# GD_Power_Meter_2.net
KiCad netlist of a schematic drawn in Altium Designer
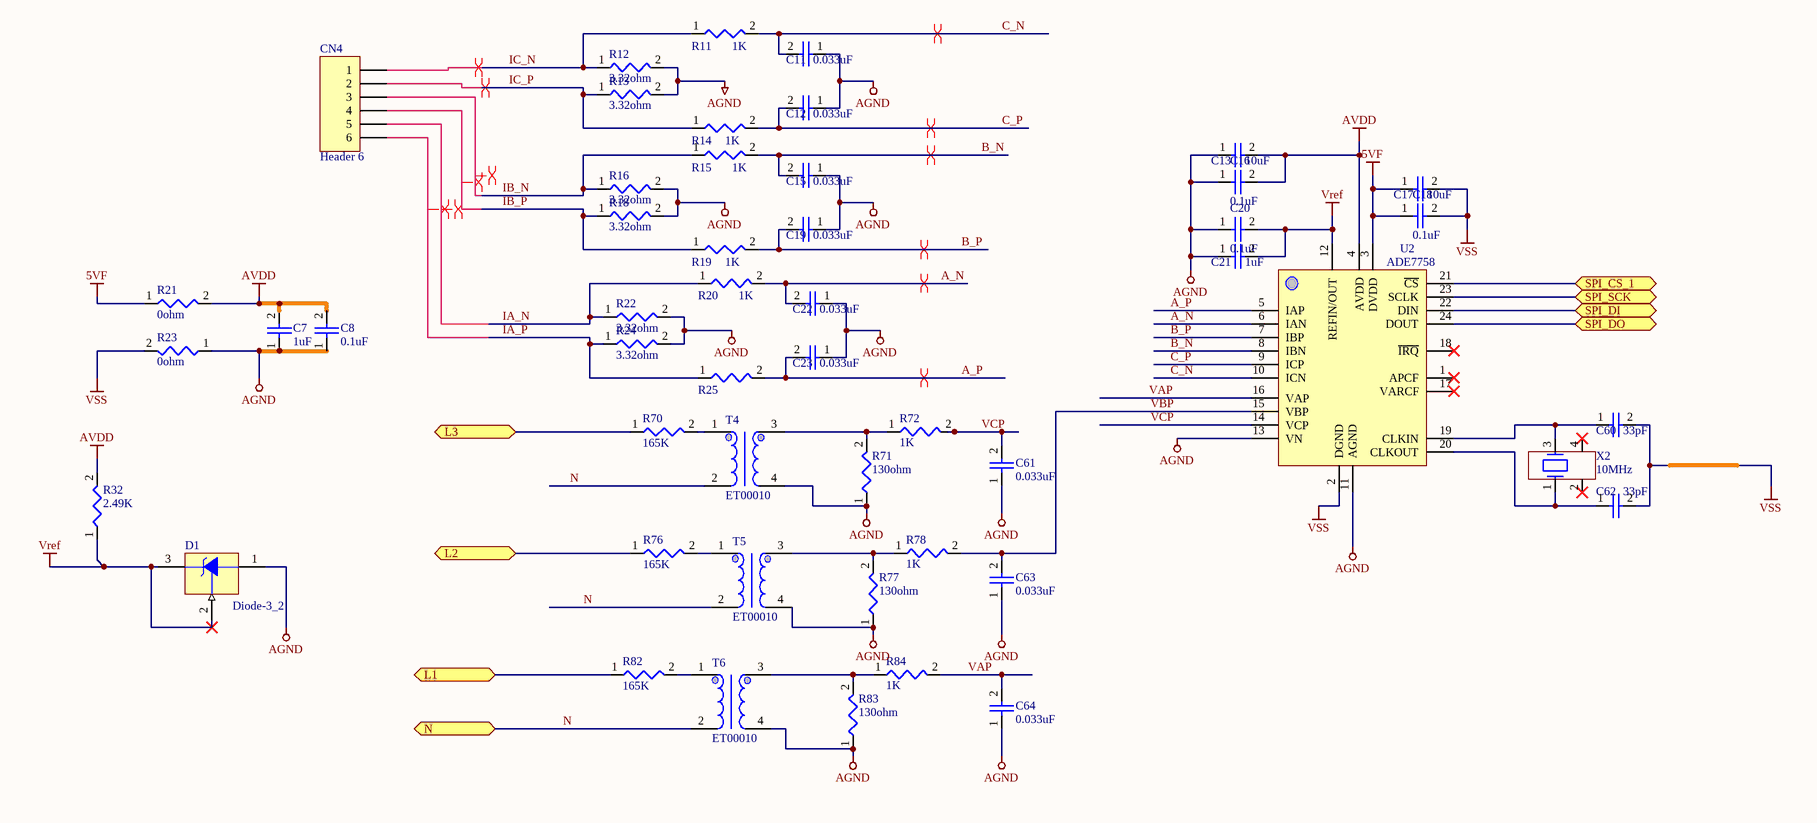
[diagram p0: GD_Power_Meter_2.SchDoc]

(export (version "E")
  (design (tool "Eeschema 10.0.6"))
  (components
    (comp (ref "C7")
      (value "1uF")
      (footprint "C0805")
      (description "CAP SMD CR X7R 50V 10% 1uF 0805 ROHS")
      (fields (field (name "MANUFACTURER") "YAGEO") (field (name "Comment") "CAP"))
      (libsource (lib "enlogic") (part "CAP"))
    )
    (comp (ref "C8")
      (value "0.1uF")
      (footprint "C0805")
      (description "CAP SMD CR X7R 50V 10% 0.1uF 0805 ROHS")
      (fields (field (name "MANUFACTURER") "YAGEO") (field (name "Comment") "CAP"))
      (libsource (lib "enlogic") (part "CAP"))
    )
    (comp (ref "C11")
      (value "0.033uF")
      (footprint "C0805")
      (description "CAP SMD X7R 50V 10% 0.033uF 0805 ROHS")
      (fields (field (name "MANUFACTURER") "Murata") (field (name "Comment") "CAP"))
      (libsource (lib "enlogic") (part "CAP"))
    )
    (comp (ref "C12")
      (value "0.033uF")
      (footprint "C0805")
      (description "CAP SMD X7R 50V 10% 0.033uF 0805 ROHS")
      (fields (field (name "MANUFACTURER") "Murata") (field (name "Comment") "CAP"))
      (libsource (lib "enlogic") (part "CAP"))
    )
    (comp (ref "C13")
      (value "10uF")
      (footprint "C0805")
      (description "CAP SMD CR X5R 16V 10% 10uF 0805 ROHS")
      (fields (field (name "MANUFACTURER") "Murata"))
      (libsource (lib "enlogic") (part "CAP"))
    )
    (comp (ref "C15")
      (value "0.033uF")
      (footprint "C0805")
      (description "CAP SMD X7R 50V 10% 0.033uF 0805 ROHS")
      (fields (field (name "MANUFACTURER") "Murata") (field (name "Comment") "CAP"))
      (libsource (lib "enlogic") (part "CAP"))
    )
    (comp (ref "C16")
      (value "0.1uF")
      (footprint "C0805")
      (description "CAP SMD CR X7R 50V 10% 0.1uF 0805 ROHS")
      (fields (field (name "MANUFACTURER") "YAGEO") (field (name "Comment") "CAP"))
      (libsource (lib "enlogic") (part "CAP"))
    )
    (comp (ref "C17")
      (value "10uF")
      (footprint "C0805")
      (description "CAP SMD CR X5R 16V 10% 10uF 0805 ROHS")
      (fields (field (name "MANUFACTURER") "Murata"))
      (libsource (lib "enlogic") (part "CAP"))
    )
    (comp (ref "C18")
      (value "0.1uF")
      (footprint "C0805")
      (description "CAP SMD CR X7R 50V 10% 0.1uF 0805 ROHS")
      (fields (field (name "MANUFACTURER") "YAGEO") (field (name "Comment") "CAP"))
      (libsource (lib "enlogic") (part "CAP"))
    )
    (comp (ref "C19")
      (value "0.033uF")
      (footprint "C0805")
      (description "CAP SMD X7R 50V 10% 0.033uF 0805 ROHS")
      (fields (field (name "MANUFACTURER") "Murata") (field (name "Comment") "CAP"))
      (libsource (lib "enlogic") (part "CAP"))
    )
    (comp (ref "C20")
      (value "0.1uF")
      (footprint "C0805")
      (description "CAP SMD CR X7R 50V 10% 0.1uF 0805 ROHS")
      (fields (field (name "MANUFACTURER") "YAGEO") (field (name "Comment") "CAP"))
      (libsource (lib "enlogic") (part "CAP"))
    )
    (comp (ref "C21")
      (value "1uF")
      (footprint "C0805")
      (description "CAP SMD CR X7R 50V 10% 1uF 0805 ROHS")
      (fields (field (name "MANUFACTURER") "YAGEO") (field (name "Comment") "CAP"))
      (libsource (lib "enlogic") (part "CAP"))
    )
    (comp (ref "C22")
      (value "0.033uF")
      (footprint "C0805")
      (description "CAP SMD X7R 50V 10% 0.033uF 0805 ROHS")
      (fields (field (name "MANUFACTURER") "Murata") (field (name "Comment") "CAP"))
      (libsource (lib "enlogic") (part "CAP"))
    )
    (comp (ref "C23")
      (value "0.033uF")
      (footprint "C0805")
      (description "CAP SMD X7R 50V 10% 0.033uF 0805 ROHS")
      (fields (field (name "MANUFACTURER") "Murata") (field (name "Comment") "CAP"))
      (libsource (lib "enlogic") (part "CAP"))
    )
    (comp (ref "C60")
      (value "33pF")
      (footprint "C0805")
      (description "CAP SMD C0G 50V 5% 33pF 0805 ROHS")
      (fields (field (name "MANUFACTURER") "YAGEO") (field (name "Comment") "CAP"))
      (libsource (lib "enlogic") (part "CAP"))
    )
    (comp (ref "C61")
      (value "0.033uF")
      (footprint "C0805")
      (description "CAP SMD X7R 50V 10% 0.033uF 0805 ROHS")
      (fields (field (name "MANUFACTURER") "Murata") (field (name "Comment") "CAP"))
      (libsource (lib "enlogic") (part "CAP"))
    )
    (comp (ref "C62")
      (value "33pF")
      (footprint "C0805")
      (description "CAP SMD C0G 50V 5% 33pF 0805 ROHS")
      (fields (field (name "MANUFACTURER") "YAGEO") (field (name "Comment") "CAP"))
      (libsource (lib "enlogic") (part "CAP"))
    )
    (comp (ref "C63")
      (value "0.033uF")
      (footprint "C0805")
      (description "CAP SMD X7R 50V 10% 0.033uF 0805 ROHS")
      (fields (field (name "MANUFACTURER") "Murata") (field (name "Comment") "CAP"))
      (libsource (lib "enlogic") (part "CAP"))
    )
    (comp (ref "C64")
      (value "0.033uF")
      (footprint "C0805")
      (description "CAP SMD X7R 50V 10% 0.033uF 0805 ROHS")
      (fields (field (name "MANUFACTURER") "Murata") (field (name "Comment") "CAP"))
      (libsource (lib "enlogic") (part "CAP"))
    )
    (comp (ref "CN4")
      (value "Header 6")
      (footprint "HT5.08-6P-H")
      (description "Header, 6-Pin")
      (libsource (lib "Enlogic_CN") (part "Header 6"))
    )
    (comp (ref "D1")
      (value "Diode-3_2")
      (footprint "SOT23-321")
      (description "IC PROGRAMMABLE PRECISION REFERENCES,2.5-20V,0.5%,SMD,ROHS")
      (fields (field (name "MANUFACTURER") "DIODES"))
      (libsource (lib "enlogic") (part "ZTL43X"))
    )
    (comp (ref "R11")
      (value "1K")
      (footprint "R0805")
      (description "RES THICK_FILM SMD 1K 1% 1/8W ROHS 0805")
      (fields (field (name "MANUFACTURER") "YAGEO") (field (name "Comment") "RES"))
      (libsource (lib "enlogic") (part "RES"))
    )
    (comp (ref "R12")
      (value "3.32ohm")
      (footprint "R0805")
      (description "RES THIN_FILM SMD 3.32 ohm 0.5% 1/8W ±50ppm/℃ ROHS 0805")
      (fields (field (name "MANUFACTURER") "YAGEO") (field (name "Comment") "RES"))
      (libsource (lib "Enlogic") (part "RES"))
    )
    (comp (ref "R13")
      (value "3.32ohm")
      (footprint "R0805")
      (description "RES THIN_FILM SMD 3.32 ohm 0.5% 1/8W ±50ppm/℃ ROHS 0805")
      (fields (field (name "MANUFACTURER") "YAGEO") (field (name "Comment") "RES"))
      (libsource (lib "Enlogic") (part "RES"))
    )
    (comp (ref "R14")
      (value "1K")
      (footprint "R0805")
      (description "RES THICK_FILM SMD 1K 1% 1/8W ROHS 0805")
      (fields (field (name "MANUFACTURER") "YAGEO") (field (name "Comment") "RES"))
      (libsource (lib "enlogic") (part "RES"))
    )
    (comp (ref "R15")
      (value "1K")
      (footprint "R0805")
      (description "RES THICK_FILM SMD 1K 1% 1/8W ROHS 0805")
      (fields (field (name "MANUFACTURER") "YAGEO") (field (name "Comment") "RES"))
      (libsource (lib "enlogic") (part "RES"))
    )
    (comp (ref "R16")
      (value "3.32ohm")
      (footprint "R0805")
      (description "RES THIN_FILM SMD 3.32 ohm 0.5% 1/8W ±50ppm/℃ ROHS 0805")
      (fields (field (name "MANUFACTURER") "YAGEO") (field (name "Comment") "RES"))
      (libsource (lib "Enlogic") (part "RES"))
    )
    (comp (ref "R18")
      (value "3.32ohm")
      (footprint "R0805")
      (description "RES THIN_FILM SMD 3.32 ohm 0.5% 1/8W ±50ppm/℃ ROHS 0805")
      (fields (field (name "MANUFACTURER") "YAGEO") (field (name "Comment") "RES"))
      (libsource (lib "Enlogic") (part "RES"))
    )
    (comp (ref "R19")
      (value "1K")
      (footprint "R0805")
      (description "RES THICK_FILM SMD 1K 1% 1/8W ROHS 0805")
      (fields (field (name "MANUFACTURER") "YAGEO") (field (name "Comment") "RES"))
      (libsource (lib "enlogic") (part "RES"))
    )
    (comp (ref "R20")
      (value "1K")
      (footprint "R0805")
      (description "RES THICK_FILM SMD 1K 1% 1/8W ROHS 0805")
      (fields (field (name "MANUFACTURER") "YAGEO") (field (name "Comment") "RES"))
      (libsource (lib "enlogic") (part "RES"))
    )
    (comp (ref "R21")
      (value "0ohm")
      (footprint "R0805")
      (description "RES THICK_FILM SMD 0 OHM 5% 1/8W ROHS 0805")
      (fields (field (name "MANUFACTURER") "YAGEO") (field (name "Comment") "RES"))
      (libsource (lib "enlogic") (part "RES"))
    )
    (comp (ref "R22")
      (value "3.32ohm")
      (footprint "R0805")
      (description "RES THIN_FILM SMD 3.32 ohm 0.5% 1/8W ±50ppm/℃ ROHS 0805")
      (fields (field (name "MANUFACTURER") "YAGEO") (field (name "Comment") "RES"))
      (libsource (lib "Enlogic") (part "RES"))
    )
    (comp (ref "R23")
      (value "0ohm")
      (footprint "R0805")
      (description "RES THICK_FILM SMD 0 OHM 5% 1/8W ROHS 0805")
      (fields (field (name "MANUFACTURER") "YAGEO") (field (name "Comment") "RES"))
      (libsource (lib "enlogic") (part "RES"))
    )
    (comp (ref "R24")
      (value "3.32ohm")
      (footprint "R0805")
      (description "RES THIN_FILM SMD 3.32 ohm 0.5% 1/8W ±50ppm/℃ ROHS 0805")
      (fields (field (name "MANUFACTURER") "YAGEO") (field (name "Comment") "RES"))
      (libsource (lib "Enlogic") (part "RES"))
    )
    (comp (ref "R25")
      (value "RES")
      (footprint "R0805")
      (description "RES THICK_FILM SMD 1K 1% 1/8W ROHS 0805")
      (fields (field (name "MANUFACTURER") "YAGEO"))
      (libsource (lib "enlogic") (part "RES"))
    )
    (comp (ref "R32")
      (value "2.49K")
      (footprint "R0805")
      (description "RES THICK_FILM 2.49K 1% 1/8W ROHS SMD 0805")
      (fields (field (name "MANUFACTURER") "YAGEO") (field (name "Comment") "RES"))
      (libsource (lib "enlogic") (part "RES"))
    )
    (comp (ref "R70")
      (value "165K")
      (footprint "MFR5W2P5")
      (description "RES Film Leaded 165K 0.5% 3W ROHS ±25ppm/℃ MFR1550")
      (fields (field (name "MANUFACTURER") "Viking") (field (name "Comment") "RES"))
      (libsource (lib "Enlogic") (part "RES"))
    )
    (comp (ref "R71")
      (value "130ohm")
      (footprint "R0805")
      (description "RES,THIN_FILM,130 ohm,0.5%	,1/10W,±25ppm/℃,ROHS,0805,SMD")
      (fields (field (name "MANUFACTURER") "VIKING") (field (name "Comment") "RES"))
      (libsource (lib "Enlogic") (part "RES"))
    )
    (comp (ref "R72")
      (value "1K")
      (footprint "R0805")
      (description "RES THICK_FILM SMD 1K 1% 1/8W ROHS 0805")
      (fields (field (name "MANUFACTURER") "YAGEO") (field (name "Comment") "RES"))
      (libsource (lib "Enlogic") (part "RES"))
    )
    (comp (ref "R76")
      (value "165K")
      (footprint "MFR5W2P5")
      (description "RES Film Leaded 165K 0.5% 3W ROHS ±25ppm/℃ MFR1550")
      (fields (field (name "MANUFACTURER") "Viking") (field (name "Comment") "RES"))
      (libsource (lib "Enlogic") (part "RES"))
    )
    (comp (ref "R77")
      (value "130ohm")
      (footprint "R0805")
      (description "RES,THIN_FILM,130 ohm,0.5%	,1/10W,±25ppm/℃,ROHS,0805,SMD")
      (fields (field (name "MANUFACTURER") "VIKING") (field (name "Comment") "RES"))
      (libsource (lib "Enlogic") (part "RES"))
    )
    (comp (ref "R78")
      (value "1K")
      (footprint "R0805")
      (description "RES THICK_FILM SMD 1K 1% 1/8W ROHS 0805")
      (fields (field (name "MANUFACTURER") "YAGEO") (field (name "Comment") "RES"))
      (libsource (lib "Enlogic") (part "RES"))
    )
    (comp (ref "R82")
      (value "165K")
      (footprint "MFR5W2P5")
      (description "RES Film Leaded 165K 0.5% 3W ROHS ±25ppm/℃ MFR1550")
      (fields (field (name "MANUFACTURER") "Viking") (field (name "Comment") "RES"))
      (libsource (lib "Enlogic") (part "RES"))
    )
    (comp (ref "R83")
      (value "130ohm")
      (footprint "R0805")
      (description "RES,THIN_FILM,130 ohm,0.5%	,1/10W,±25ppm/℃,ROHS,0805,SMD")
      (fields (field (name "MANUFACTURER") "VIKING") (field (name "Comment") "RES"))
      (libsource (lib "Enlogic") (part "RES"))
    )
    (comp (ref "R84")
      (value "1K")
      (footprint "R0805")
      (description "RES THICK_FILM SMD 1K 1% 1/8W ROHS 0805")
      (fields (field (name "MANUFACTURER") "YAGEO") (field (name "Comment") "RES"))
      (libsource (lib "Enlogic") (part "RES"))
    )
    (comp (ref "T4")
      (value "ET00010")
      (footprint "ZMPT107")
      (description "Voltage transformer,2mA/2mA,THT,ROHS")
      (fields (field (name "MANUFACTURER") "ZEMING"))
      (libsource (lib "Enlogic") (part "ZMPT107"))
    )
    (comp (ref "T5")
      (value "ET00010")
      (footprint "ZMPT107")
      (description "Voltage transformer,2mA/2mA,THT,ROHS")
      (fields (field (name "MANUFACTURER") "ZEMING"))
      (libsource (lib "Enlogic") (part "ZMPT107"))
    )
    (comp (ref "T6")
      (value "ET00010")
      (footprint "ZMPT107")
      (description "Voltage transformer,2mA/2mA,THT,ROHS")
      (fields (field (name "MANUFACTURER") "ZEMING"))
      (libsource (lib "Enlogic") (part "ZMPT107"))
    )
    (comp (ref "U2")
      (value "ADE7758")
      (footprint "SOIC24-W")
      (description "IC Energy Measurement,Irms,VA,VAR,Vrms,Watt,Output:Pulsed&SPI,SOIC_W-24,ROHS")
      (fields (field (name "MANUFACTURER") "ANALOG DEVICES"))
      (libsource (lib "enlogic") (part "ADE7758"))
    )
    (comp (ref "X2")
      (value "10MHz")
      (footprint "XTAL_5X3_2")
      (description "XTAL 10MHz 18PF +/-30PPM,3.2mmWx5mmLx1.3mmH,-40~85,RoHS,SMD")
      (fields (field (name "MANUFACTURER") "ABRACON") (field (name "Comment") "ABM3C"))
      (libsource (lib "enlogic") (part "ABM3C"))
    )
  )
  (nets
    (net (code "1") (name "/A_N") (class "Default")
      (node (ref "C22") (pin "2") (pinfunction "2_2") (pintype "passive"))
      (node (ref "R20") (pin "2") (pinfunction "2_2") (pintype "passive"))
      (node (ref "U2") (pin "6") (pinfunction "IAN_6") (pintype "passive"))
    )
    (net (code "2") (name "/A_P") (class "Default")
      (node (ref "C23") (pin "2") (pinfunction "2_2") (pintype "passive"))
      (node (ref "R25") (pin "2") (pinfunction "2_2") (pintype "passive"))
      (node (ref "U2") (pin "5") (pinfunction "IAP_5") (pintype "passive"))
    )
    (net (code "3") (name "/B_N") (class "Default")
      (node (ref "C15") (pin "2") (pinfunction "2_2") (pintype "passive"))
      (node (ref "R15") (pin "2") (pinfunction "2_2") (pintype "passive"))
      (node (ref "U2") (pin "8") (pinfunction "IBN_8") (pintype "passive"))
    )
    (net (code "4") (name "/B_P") (class "Default")
      (node (ref "C19") (pin "2") (pinfunction "2_2") (pintype "passive"))
      (node (ref "R19") (pin "2") (pinfunction "2_2") (pintype "passive"))
      (node (ref "U2") (pin "7") (pinfunction "IBP_7") (pintype "passive"))
    )
    (net (code "5") (name "/C_N") (class "Default")
      (node (ref "C11") (pin "2") (pinfunction "2_2") (pintype "passive"))
      (node (ref "R11") (pin "2") (pinfunction "2_2") (pintype "passive"))
      (node (ref "U2") (pin "10") (pinfunction "ICN_10") (pintype "passive"))
    )
    (net (code "6") (name "/C_P") (class "Default")
      (node (ref "C12") (pin "2") (pinfunction "2_2") (pintype "passive"))
      (node (ref "R14") (pin "2") (pinfunction "2_2") (pintype "passive"))
      (node (ref "U2") (pin "9") (pinfunction "ICP_9") (pintype "passive"))
    )
    (net (code "7") (name "/IA_N") (class "Default")
      (node (ref "CN4") (pin "5") (pinfunction "5_5") (pintype "passive"))
      (node (ref "R20") (pin "1") (pinfunction "1_1") (pintype "passive"))
      (node (ref "R22") (pin "1") (pinfunction "1_1") (pintype "passive"))
    )
    (net (code "8") (name "/IA_P") (class "Default")
      (node (ref "CN4") (pin "6") (pinfunction "6_6") (pintype "passive"))
      (node (ref "R24") (pin "1") (pinfunction "1_1") (pintype "passive"))
      (node (ref "R25") (pin "1") (pinfunction "1_1") (pintype "passive"))
    )
    (net (code "9") (name "/IB_N") (class "Default")
      (node (ref "CN4") (pin "3") (pinfunction "3_3") (pintype "passive"))
      (node (ref "R15") (pin "1") (pinfunction "1_1") (pintype "passive"))
      (node (ref "R16") (pin "1") (pinfunction "1_1") (pintype "passive"))
    )
    (net (code "10") (name "/IB_P") (class "Default")
      (node (ref "CN4") (pin "4") (pinfunction "4_4") (pintype "passive"))
      (node (ref "R18") (pin "1") (pinfunction "1_1") (pintype "passive"))
      (node (ref "R19") (pin "1") (pinfunction "1_1") (pintype "passive"))
    )
    (net (code "11") (name "/IC_N") (class "Default")
      (node (ref "CN4") (pin "1") (pinfunction "1_1") (pintype "passive"))
      (node (ref "R11") (pin "1") (pinfunction "1_1") (pintype "passive"))
      (node (ref "R12") (pin "1") (pinfunction "1_1") (pintype "passive"))
    )
    (net (code "12") (name "/IC_P") (class "Default")
      (node (ref "CN4") (pin "2") (pinfunction "2_2") (pintype "passive"))
      (node (ref "R13") (pin "1") (pinfunction "1_1") (pintype "passive"))
      (node (ref "R14") (pin "1") (pinfunction "1_1") (pintype "passive"))
    )
    (net (code "13") (name "/L1") (class "Default")
      (node (ref "R82") (pin "1") (pinfunction "1_1") (pintype "passive"))
    )
    (net (code "14") (name "/L2") (class "Default")
      (node (ref "R76") (pin "1") (pinfunction "1_1") (pintype "passive"))
    )
    (net (code "15") (name "/L3") (class "Default")
      (node (ref "R70") (pin "1") (pinfunction "1_1") (pintype "passive"))
    )
    (net (code "16") (name "/N") (class "Default")
      (node (ref "T4") (pin "2") (pinfunction "2_2") (pintype "passive"))
      (node (ref "T5") (pin "2") (pinfunction "2_2") (pintype "passive"))
      (node (ref "T6") (pin "2") (pinfunction "2_2") (pintype "passive"))
    )
    (net (code "17") (name "/SPI_CS_1") (class "Default")
      (node (ref "U2") (pin "21") (pinfunction "~{CS}_21") (pintype "passive"))
    )
    (net (code "18") (name "/SPI_DI") (class "Default")
      (node (ref "U2") (pin "22") (pinfunction "DIN_22") (pintype "passive"))
    )
    (net (code "19") (name "/SPI_DO") (class "Default")
      (node (ref "U2") (pin "24") (pinfunction "DOUT_24") (pintype "passive"))
    )
    (net (code "20") (name "/SPI_SCK") (class "Default")
      (node (ref "U2") (pin "23") (pinfunction "SCLK_23") (pintype "passive"))
    )
    (net (code "21") (name "/VAP") (class "Default")
      (node (ref "C64") (pin "2") (pinfunction "2_2") (pintype "passive"))
      (node (ref "R84") (pin "2") (pinfunction "2_2") (pintype "passive"))
      (node (ref "U2") (pin "16") (pinfunction "VAP_16") (pintype "passive"))
    )
    (net (code "22") (name "/VBP") (class "Default")
      (node (ref "C63") (pin "2") (pinfunction "2_2") (pintype "passive"))
      (node (ref "R78") (pin "2") (pinfunction "2_2") (pintype "passive"))
      (node (ref "U2") (pin "15") (pinfunction "VBP_15") (pintype "passive"))
    )
    (net (code "23") (name "/VCP") (class "Default")
      (node (ref "C61") (pin "2") (pinfunction "2_2") (pintype "passive"))
      (node (ref "R72") (pin "2") (pinfunction "2_2") (pintype "passive"))
      (node (ref "U2") (pin "14") (pinfunction "VCP_14") (pintype "passive"))
    )
    (net (code "24") (name "5VF") (class "Default")
      (node (ref "C17") (pin "1") (pinfunction "1_1") (pintype "passive"))
      (node (ref "C18") (pin "1") (pinfunction "1_1") (pintype "passive"))
      (node (ref "R21") (pin "1") (pinfunction "1_1") (pintype "passive"))
      (node (ref "U2") (pin "3") (pinfunction "DVDD_3") (pintype "passive"))
    )
    (net (code "25") (name "AGND") (class "Default")
      (node (ref "C11") (pin "1") (pinfunction "1_1") (pintype "passive"))
      (node (ref "C12") (pin "1") (pinfunction "1_1") (pintype "passive"))
      (node (ref "C13") (pin "1") (pinfunction "1_1") (pintype "passive"))
      (node (ref "C15") (pin "1") (pinfunction "1_1") (pintype "passive"))
      (node (ref "C16") (pin "1") (pinfunction "1_1") (pintype "passive"))
      (node (ref "C19") (pin "1") (pinfunction "1_1") (pintype "passive"))
      (node (ref "C20") (pin "1") (pinfunction "1_1") (pintype "passive"))
      (node (ref "C21") (pin "1") (pinfunction "1_1") (pintype "passive"))
      (node (ref "C22") (pin "1") (pinfunction "1_1") (pintype "passive"))
      (node (ref "C23") (pin "1") (pinfunction "1_1") (pintype "passive"))
      (node (ref "C61") (pin "1") (pinfunction "1_1") (pintype "passive"))
      (node (ref "C63") (pin "1") (pinfunction "1_1") (pintype "passive"))
      (node (ref "C64") (pin "1") (pinfunction "1_1") (pintype "passive"))
      (node (ref "C7") (pin "1") (pinfunction "1_1") (pintype "passive"))
      (node (ref "C8") (pin "1") (pinfunction "1_1") (pintype "passive"))
      (node (ref "D1") (pin "1") (pinfunction "A_1") (pintype "passive"))
      (node (ref "R12") (pin "2") (pinfunction "2_2") (pintype "passive"))
      (node (ref "R13") (pin "2") (pinfunction "2_2") (pintype "passive"))
      (node (ref "R16") (pin "2") (pinfunction "2_2") (pintype "passive"))
      (node (ref "R18") (pin "2") (pinfunction "2_2") (pintype "passive"))
      (node (ref "R22") (pin "2") (pinfunction "2_2") (pintype "passive"))
      (node (ref "R23") (pin "1") (pinfunction "1_1") (pintype "passive"))
      (node (ref "R24") (pin "2") (pinfunction "2_2") (pintype "passive"))
      (node (ref "R71") (pin "1") (pinfunction "1_1") (pintype "passive"))
      (node (ref "R77") (pin "1") (pinfunction "1_1") (pintype "passive"))
      (node (ref "R83") (pin "1") (pinfunction "1_1") (pintype "passive"))
      (node (ref "T4") (pin "4") (pinfunction "4_4") (pintype "passive"))
      (node (ref "T5") (pin "4") (pinfunction "4_4") (pintype "passive"))
      (node (ref "T6") (pin "4") (pinfunction "4_4") (pintype "passive"))
      (node (ref "U2") (pin "11") (pinfunction "AGND_11") (pintype "passive"))
      (node (ref "U2") (pin "13") (pinfunction "VN_13") (pintype "passive"))
    )
    (net (code "26") (name "AVDD") (class "Default")
      (node (ref "C13") (pin "2") (pinfunction "2_2") (pintype "passive"))
      (node (ref "C16") (pin "2") (pinfunction "2_2") (pintype "passive"))
      (node (ref "C7") (pin "2") (pinfunction "2_2") (pintype "passive"))
      (node (ref "C8") (pin "2") (pinfunction "2_2") (pintype "passive"))
      (node (ref "R21") (pin "2") (pinfunction "2_2") (pintype "passive"))
      (node (ref "R32") (pin "2") (pinfunction "2_2") (pintype "passive"))
      (node (ref "U2") (pin "4") (pinfunction "AVDD_4") (pintype "passive"))
    )
    (net (code "27") (name "Net-(R70-Pad2)") (class "Default")
      (node (ref "R70") (pin "2") (pinfunction "2_2") (pintype "passive"))
      (node (ref "T4") (pin "1") (pinfunction "1_1") (pintype "passive"))
    )
    (net (code "28") (name "Net-(R71-Pad2)") (class "Default")
      (node (ref "R71") (pin "2") (pinfunction "2_2") (pintype "passive"))
      (node (ref "R72") (pin "1") (pinfunction "1_1") (pintype "passive"))
      (node (ref "T4") (pin "3") (pinfunction "3_3") (pintype "passive"))
    )
    (net (code "29") (name "Net-(R76-Pad2)") (class "Default")
      (node (ref "R76") (pin "2") (pinfunction "2_2") (pintype "passive"))
      (node (ref "T5") (pin "1") (pinfunction "1_1") (pintype "passive"))
    )
    (net (code "30") (name "Net-(R77-Pad2)") (class "Default")
      (node (ref "R77") (pin "2") (pinfunction "2_2") (pintype "passive"))
      (node (ref "R78") (pin "1") (pinfunction "1_1") (pintype "passive"))
      (node (ref "T5") (pin "3") (pinfunction "3_3") (pintype "passive"))
    )
    (net (code "31") (name "Net-(R82-Pad2)") (class "Default")
      (node (ref "R82") (pin "2") (pinfunction "2_2") (pintype "passive"))
      (node (ref "T6") (pin "1") (pinfunction "1_1") (pintype "passive"))
    )
    (net (code "32") (name "Net-(R83-Pad2)") (class "Default")
      (node (ref "R83") (pin "2") (pinfunction "2_2") (pintype "passive"))
      (node (ref "R84") (pin "1") (pinfunction "1_1") (pintype "passive"))
      (node (ref "T6") (pin "3") (pinfunction "3_3") (pintype "passive"))
    )
    (net (code "33") (name "Net-(U2-CLKIN)") (class "Default")
      (node (ref "C60") (pin "1") (pinfunction "1_1") (pintype "passive"))
      (node (ref "U2") (pin "19") (pinfunction "CLKIN_19") (pintype "passive"))
      (node (ref "X2") (pin "3") (pinfunction "3_3") (pintype "passive"))
    )
    (net (code "34") (name "Net-(U2-CLKOUT)") (class "Default")
      (node (ref "C62") (pin "1") (pinfunction "1_1") (pintype "passive"))
      (node (ref "U2") (pin "20") (pinfunction "CLKOUT_20") (pintype "passive"))
      (node (ref "X2") (pin "1") (pinfunction "1_1") (pintype "passive"))
    )
    (net (code "35") (name "VSS") (class "Default")
      (node (ref "C17") (pin "2") (pinfunction "2_2") (pintype "passive"))
      (node (ref "C18") (pin "2") (pinfunction "2_2") (pintype "passive"))
      (node (ref "C60") (pin "2") (pinfunction "2_2") (pintype "passive"))
      (node (ref "C62") (pin "2") (pinfunction "2_2") (pintype "passive"))
      (node (ref "R23") (pin "2") (pinfunction "2_2") (pintype "passive"))
      (node (ref "U2") (pin "2") (pinfunction "DGND_2") (pintype "passive"))
    )
    (net (code "36") (name "Vref") (class "Default")
      (node (ref "C20") (pin "2") (pinfunction "2_2") (pintype "passive"))
      (node (ref "C21") (pin "2") (pinfunction "2_2") (pintype "passive"))
      (node (ref "D1") (pin "2") (pinfunction "R_2") (pintype "input"))
      (node (ref "D1") (pin "3") (pinfunction "C_3") (pintype "passive"))
      (node (ref "R32") (pin "1") (pinfunction "1_1") (pintype "passive"))
      (node (ref "U2") (pin "12") (pinfunction "REFIN/OUT_12") (pintype "passive"))
    )
    (net (code "37") (name "unconnected-(U2-APCF-Pad1)") (class "Default")
      (node (ref "U2") (pin "1") (pinfunction "APCF_1") (pintype "passive+no_connect"))
    )
    (net (code "38") (name "unconnected-(U2-VARCF-Pad17)") (class "Default")
      (node (ref "U2") (pin "17") (pinfunction "VARCF_17") (pintype "passive+no_connect"))
    )
    (net (code "39") (name "unconnected-(U2-~{IRQ}-Pad18)") (class "Default")
      (node (ref "U2") (pin "18") (pinfunction "~{IRQ}_18") (pintype "passive+no_connect"))
    )
    (net (code "40") (name "unconnected-(X2-Pad2)") (class "Default")
      (node (ref "X2") (pin "2") (pinfunction "2_2") (pintype "passive+no_connect"))
    )
    (net (code "41") (name "unconnected-(X2-Pad4)") (class "Default")
      (node (ref "X2") (pin "4") (pinfunction "4_4") (pintype "passive+no_connect"))
    )
  )
)
